# Handschuh.net
KiCad netlist of a schematic drawn in EAGLE
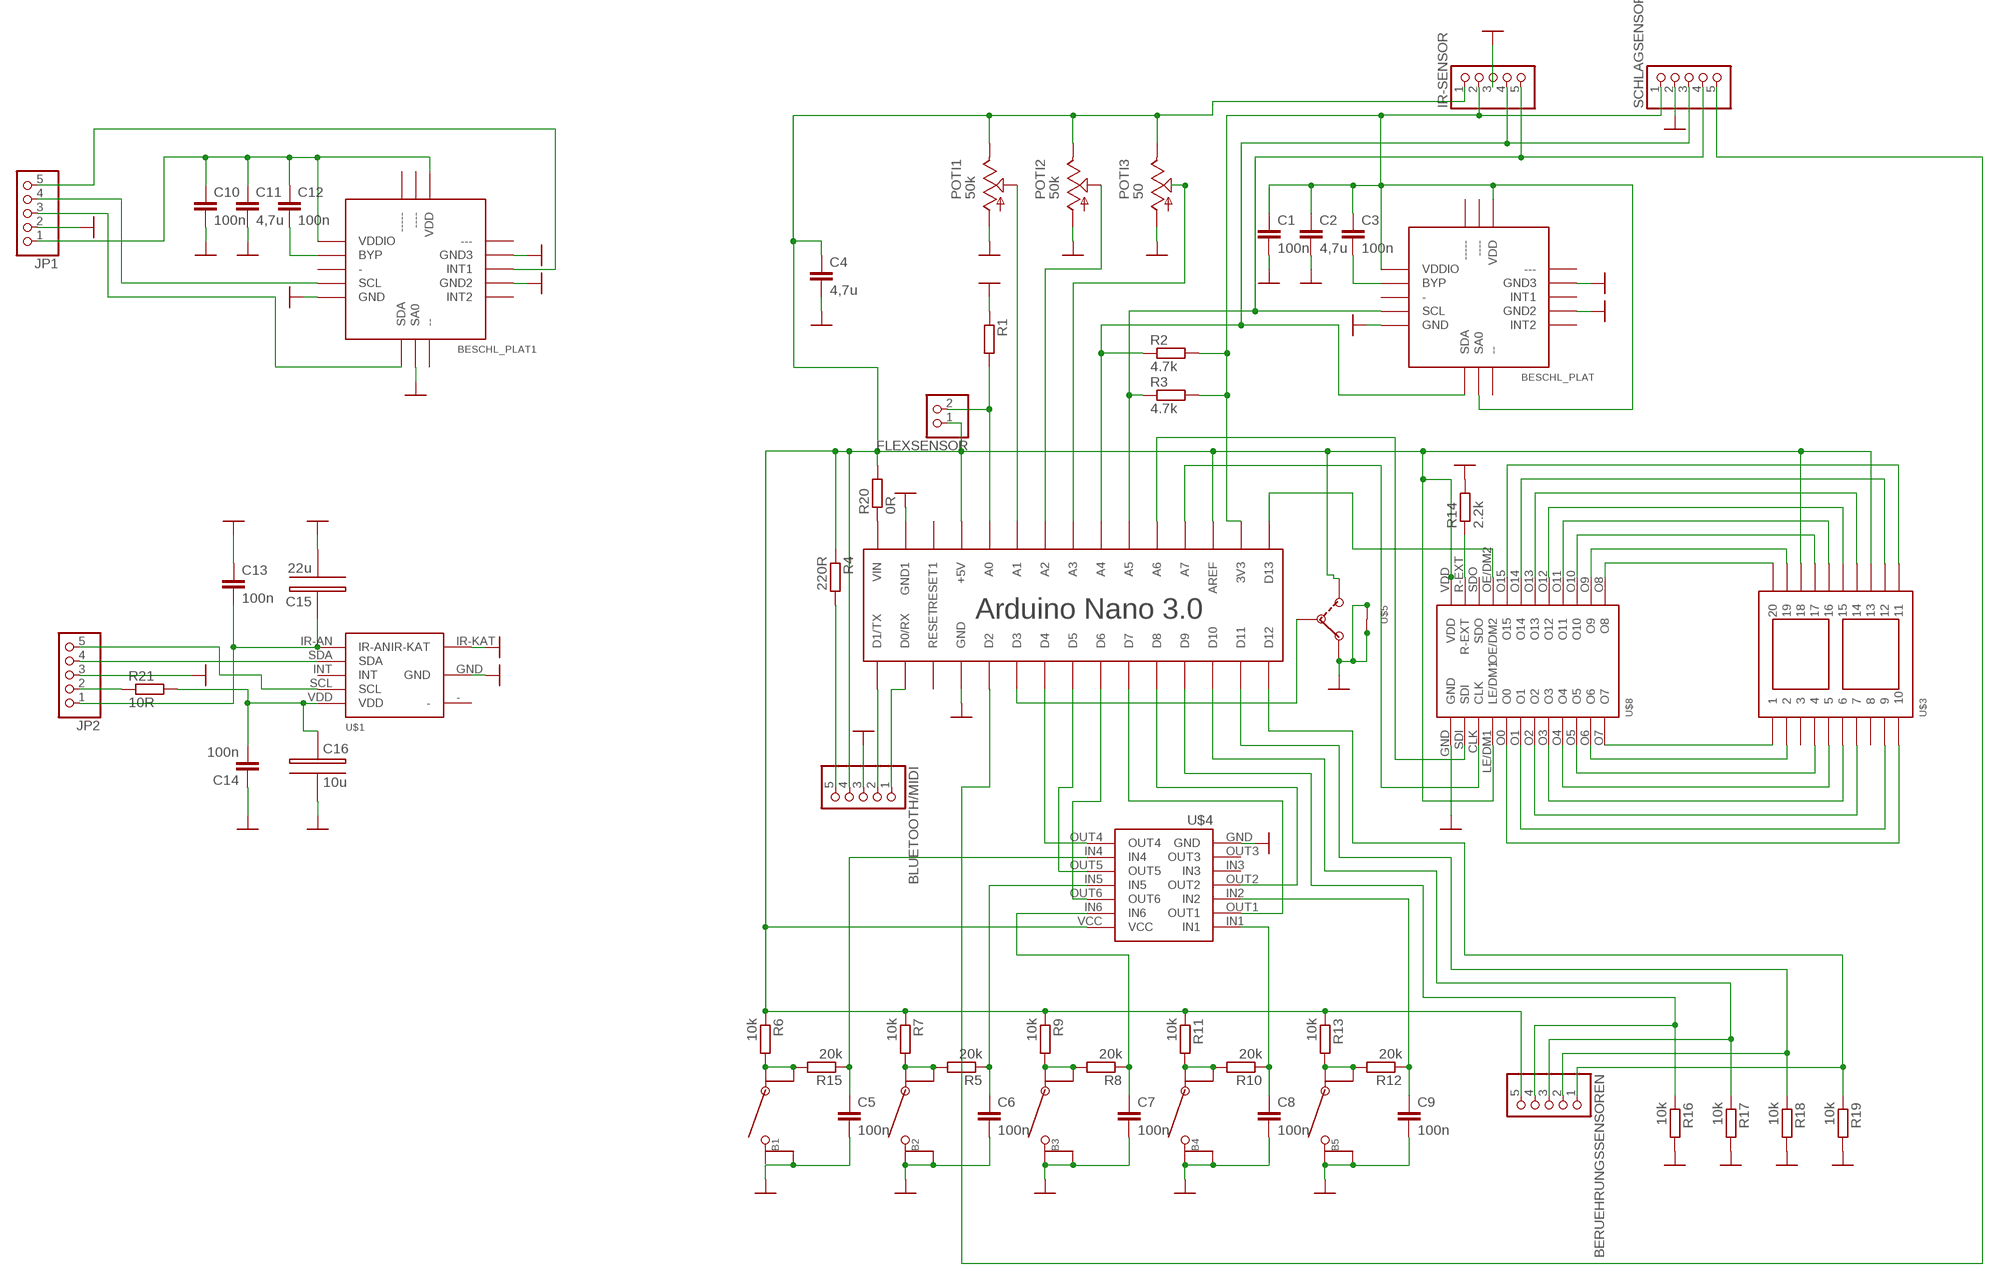
[diagram p0: schematic, sheet 1]

(export (version "E")
  (design (tool "Eeschema 10.0.6"))
  (components
    (comp (ref "B1")
      (value "BUTTON")
      (footprint "eagle-import:BUTTON")
      (libsource (lib "eagle-import") (part "BUTTON"))
    )
    (comp (ref "B2")
      (value "BUTTON")
      (footprint "eagle-import:BUTTON")
      (libsource (lib "eagle-import") (part "BUTTON"))
    )
    (comp (ref "B3")
      (value "BUTTON")
      (footprint "eagle-import:BUTTON")
      (libsource (lib "eagle-import") (part "BUTTON"))
    )
    (comp (ref "B4")
      (value "BUTTON")
      (footprint "eagle-import:BUTTON")
      (libsource (lib "eagle-import") (part "BUTTON"))
    )
    (comp (ref "B5")
      (value "BUTTON")
      (footprint "eagle-import:BUTTON")
      (libsource (lib "eagle-import") (part "BUTTON"))
    )
    (comp (ref "BERUEHRUNGSSENSOREN")
      (value "PINHD-1X5/90")
      (footprint "eagle-import:1X05_90")
      (libsource (lib "eagle-import") (part "PINHD-1X5/90"))
    )
    (comp (ref "BESCHL_PLAT")
      (value "BESCHLEUNIGSUNGSSENSOR")
      (footprint "eagle-import:BESCHLEUNIGUNGSSENSOR")
      (libsource (lib "eagle-import") (part "BESCHLEUNIGSUNGSSENSOR"))
    )
    (comp (ref "BESCHL_PLAT1")
      (value "BESCHLEUNIGSUNGSSENSOR")
      (footprint "eagle-import:BESCHLEUNIGUNGSSENSOR")
      (libsource (lib "eagle-import") (part "BESCHLEUNIGSUNGSSENSOR"))
    )
    (comp (ref "BLUETOOTH/MIDI")
      (value "PINHD-1X5/90")
      (footprint "eagle-import:1X05_90")
      (libsource (lib "eagle-import") (part "PINHD-1X5/90"))
    )
    (comp (ref "C1")
      (value "100n")
      (footprint "eagle-import:C0805")
      (libsource (lib "eagle-import") (part "C-EUC0805"))
    )
    (comp (ref "C2")
      (value "4,7u")
      (footprint "eagle-import:C0805")
      (libsource (lib "eagle-import") (part "C-EUC0805"))
    )
    (comp (ref "C3")
      (value "100n")
      (footprint "eagle-import:C0805")
      (libsource (lib "eagle-import") (part "C-EUC0805"))
    )
    (comp (ref "C4")
      (value "4,7u")
      (footprint "eagle-import:C0805")
      (libsource (lib "eagle-import") (part "C-EUC0805"))
    )
    (comp (ref "C5")
      (value "100n")
      (footprint "eagle-import:C0805")
      (libsource (lib "eagle-import") (part "C-EUC0805"))
    )
    (comp (ref "C6")
      (value "100n")
      (footprint "eagle-import:C0805")
      (libsource (lib "eagle-import") (part "C-EUC0805"))
    )
    (comp (ref "C7")
      (value "100n")
      (footprint "eagle-import:C0805")
      (libsource (lib "eagle-import") (part "C-EUC0805"))
    )
    (comp (ref "C8")
      (value "100n")
      (footprint "eagle-import:C0805")
      (libsource (lib "eagle-import") (part "C-EUC0805"))
    )
    (comp (ref "C9")
      (value "100n")
      (footprint "eagle-import:C0805")
      (libsource (lib "eagle-import") (part "C-EUC0805"))
    )
    (comp (ref "C10")
      (value "100n")
      (footprint "eagle-import:C0805")
      (libsource (lib "eagle-import") (part "C-EUC0805"))
    )
    (comp (ref "C11")
      (value "4,7u")
      (footprint "eagle-import:C0805")
      (libsource (lib "eagle-import") (part "C-EUC0805"))
    )
    (comp (ref "C12")
      (value "100n")
      (footprint "eagle-import:C0805")
      (libsource (lib "eagle-import") (part "C-EUC0805"))
    )
    (comp (ref "C13")
      (value "100n")
      (footprint "eagle-import:C0805")
      (libsource (lib "eagle-import") (part "C-EUC0805"))
    )
    (comp (ref "C14")
      (value "100n")
      (footprint "eagle-import:C0805")
      (libsource (lib "eagle-import") (part "C-EUC0805"))
    )
    (comp (ref "C15")
      (value "22u")
      (footprint "eagle-import:22U-KONDENSATOR")
      (libsource (lib "eagle-import") (part "22U-KONDENSATOR"))
    )
    (comp (ref "C16")
      (value "10u")
      (footprint "eagle-import:22U-KONDENSATOR")
      (libsource (lib "eagle-import") (part "22U-KONDENSATOR"))
    )
    (comp (ref "FLEXSENSOR")
      (value "PINHD-1X2/90")
      (footprint "eagle-import:1X02_90")
      (libsource (lib "eagle-import") (part "PINHD-1X2/90"))
    )
    (comp (ref "IR-SENSOR")
      (value "PINHD-1X5/90")
      (footprint "eagle-import:1X05_90")
      (libsource (lib "eagle-import") (part "PINHD-1X5/90"))
    )
    (comp (ref "JP1")
      (value "PINHD-1X5/90")
      (footprint "eagle-import:1X05_90")
      (libsource (lib "eagle-import") (part "PINHD-1X5/90"))
    )
    (comp (ref "JP2")
      (value "PINHD-1X5/90")
      (footprint "eagle-import:1X05_90")
      (libsource (lib "eagle-import") (part "PINHD-1X5/90"))
    )
    (comp (ref "POTI1")
      (value "50k")
      (footprint "eagle-import:POTI")
      (libsource (lib "eagle-import") (part "POTI"))
    )
    (comp (ref "POTI2")
      (value "50k")
      (footprint "eagle-import:POTI")
      (libsource (lib "eagle-import") (part "POTI"))
    )
    (comp (ref "POTI3")
      (value "50")
      (footprint "eagle-import:POTI")
      (libsource (lib "eagle-import") (part "POTI"))
    )
    (comp (ref "R1")
      (value "R-EU_M0805")
      (footprint "eagle-import:M0805")
      (libsource (lib "eagle-import") (part "R-EU_M0805"))
    )
    (comp (ref "R2")
      (value "4.7k")
      (footprint "eagle-import:M0805")
      (libsource (lib "eagle-import") (part "R-EU_M0805"))
    )
    (comp (ref "R3")
      (value "4.7k")
      (footprint "eagle-import:M0805")
      (libsource (lib "eagle-import") (part "R-EU_M0805"))
    )
    (comp (ref "R4")
      (value "220R")
      (footprint "eagle-import:M0805")
      (libsource (lib "eagle-import") (part "R-EU_M0805"))
    )
    (comp (ref "R5")
      (value "20k")
      (footprint "eagle-import:M0805")
      (libsource (lib "eagle-import") (part "R-EU_M0805"))
    )
    (comp (ref "R6")
      (value "10k")
      (footprint "eagle-import:M0805")
      (libsource (lib "eagle-import") (part "R-EU_M0805"))
    )
    (comp (ref "R7")
      (value "10k")
      (footprint "eagle-import:M0805")
      (libsource (lib "eagle-import") (part "R-EU_M0805"))
    )
    (comp (ref "R8")
      (value "20k")
      (footprint "eagle-import:M0805")
      (libsource (lib "eagle-import") (part "R-EU_M0805"))
    )
    (comp (ref "R9")
      (value "10k")
      (footprint "eagle-import:M0805")
      (libsource (lib "eagle-import") (part "R-EU_M0805"))
    )
    (comp (ref "R10")
      (value "20k")
      (footprint "eagle-import:M0805")
      (libsource (lib "eagle-import") (part "R-EU_M0805"))
    )
    (comp (ref "R11")
      (value "10k")
      (footprint "eagle-import:M0805")
      (libsource (lib "eagle-import") (part "R-EU_M0805"))
    )
    (comp (ref "R12")
      (value "20k")
      (footprint "eagle-import:M0805")
      (libsource (lib "eagle-import") (part "R-EU_M0805"))
    )
    (comp (ref "R13")
      (value "10k")
      (footprint "eagle-import:M0805")
      (libsource (lib "eagle-import") (part "R-EU_M0805"))
    )
    (comp (ref "R14")
      (value "2.2k")
      (footprint "eagle-import:M0805")
      (libsource (lib "eagle-import") (part "R-EU_M0805"))
    )
    (comp (ref "R15")
      (value "20k")
      (footprint "eagle-import:M0805")
      (libsource (lib "eagle-import") (part "R-EU_M0805"))
    )
    (comp (ref "R16")
      (value "10k")
      (footprint "eagle-import:M0805")
      (libsource (lib "eagle-import") (part "R-EU_M0805"))
    )
    (comp (ref "R17")
      (value "10k")
      (footprint "eagle-import:M0805")
      (libsource (lib "eagle-import") (part "R-EU_M0805"))
    )
    (comp (ref "R18")
      (value "10k")
      (footprint "eagle-import:M0805")
      (libsource (lib "eagle-import") (part "R-EU_M0805"))
    )
    (comp (ref "R19")
      (value "10k")
      (footprint "eagle-import:M0805")
      (libsource (lib "eagle-import") (part "R-EU_M0805"))
    )
    (comp (ref "R20")
      (value "0R")
      (footprint "eagle-import:M0805")
      (libsource (lib "eagle-import") (part "R-EU_M0805"))
    )
    (comp (ref "R21")
      (value "10R")
      (footprint "eagle-import:M0805")
      (libsource (lib "eagle-import") (part "R-EU_M0805"))
    )
    (comp (ref "SCHLAGSENSOR")
      (value "PINHD-1X5/90")
      (footprint "eagle-import:1X05_90")
      (libsource (lib "eagle-import") (part "PINHD-1X5/90"))
    )
    (comp (ref "U$1")
      (value "IR-SENSOR")
      (footprint "eagle-import:IR-SENSOR")
      (libsource (lib "eagle-import") (part "IR-SENSOR"))
    )
    (comp (ref "U$2")
      (value "ARDUINONANO")
      (footprint "eagle-import:PDIP-32")
      (libsource (lib "eagle-import") (part "ARDUINONANO"))
    )
    (comp (ref "U$3")
      (value "7-SEGMENT")
      (footprint "eagle-import:7-SEGMENT")
      (libsource (lib "eagle-import") (part "7-SEGMENT"))
    )
    (comp (ref "U$4")
      (value "SCHMITT-TRIGGER")
      (footprint "eagle-import:SCHMITT-TRIGGER")
      (libsource (lib "eagle-import") (part "SCHMITT-TRIGGER"))
    )
    (comp (ref "U$5")
      (value "SCHALTER")
      (footprint "eagle-import:SCHALTER")
      (libsource (lib "eagle-import") (part "SCHALTER"))
    )
    (comp (ref "U$8")
      (value "7-SEGMENT-TREIBER")
      (footprint "eagle-import:7-SEGMENT-TREIBER")
      (libsource (lib "eagle-import") (part "7-SEGMENT-TREIBER"))
    )
  )
  (nets
    (net (code "1") (name "Net-(B1-Pad3)") (class "Default")
      (node (ref "B1") (pin "3") (pinfunction "3_3") (pintype "bidirectional"))
      (node (ref "B1") (pin "4") (pinfunction "4_4") (pintype "bidirectional"))
      (node (ref "R15") (pin "2") (pinfunction "2_2") (pintype "passive"))
      (node (ref "R6") (pin "2") (pinfunction "2_2") (pintype "passive"))
    )
    (net (code "2") (name "Net-(B2-Pad3)") (class "Default")
      (node (ref "B2") (pin "3") (pinfunction "3_3") (pintype "bidirectional"))
      (node (ref "B2") (pin "4") (pinfunction "4_4") (pintype "bidirectional"))
      (node (ref "R5") (pin "2") (pinfunction "2_2") (pintype "passive"))
      (node (ref "R7") (pin "2") (pinfunction "2_2") (pintype "passive"))
    )
    (net (code "3") (name "Net-(B3-Pad3)") (class "Default")
      (node (ref "B3") (pin "3") (pinfunction "3_3") (pintype "bidirectional"))
      (node (ref "B3") (pin "4") (pinfunction "4_4") (pintype "bidirectional"))
      (node (ref "R8") (pin "2") (pinfunction "2_2") (pintype "passive"))
      (node (ref "R9") (pin "2") (pinfunction "2_2") (pintype "passive"))
    )
    (net (code "4") (name "Net-(B4-Pad3)") (class "Default")
      (node (ref "B4") (pin "3") (pinfunction "3_3") (pintype "bidirectional"))
      (node (ref "B4") (pin "4") (pinfunction "4_4") (pintype "bidirectional"))
      (node (ref "R10") (pin "2") (pinfunction "2_2") (pintype "passive"))
      (node (ref "R11") (pin "2") (pinfunction "2_2") (pintype "passive"))
    )
    (net (code "5") (name "Net-(B5-Pad3)") (class "Default")
      (node (ref "B5") (pin "3") (pinfunction "3_3") (pintype "bidirectional"))
      (node (ref "B5") (pin "4") (pinfunction "4_4") (pintype "bidirectional"))
      (node (ref "R12") (pin "2") (pinfunction "2_2") (pintype "passive"))
      (node (ref "R13") (pin "2") (pinfunction "2_2") (pintype "passive"))
    )
    (net (code "6") (name "Net-(BERUEHRUNGSSENSOREN-Pad1)") (class "Default")
      (node (ref "BERUEHRUNGSSENSOREN") (pin "1") (pinfunction "1_1") (pintype "passive"))
      (node (ref "R19") (pin "1") (pinfunction "1_1") (pintype "passive"))
      (node (ref "U$2") (pin "D12") (pinfunction "D12_D12") (pintype "bidirectional"))
    )
    (net (code "7") (name "Net-(BERUEHRUNGSSENSOREN-Pad2)") (class "Default")
      (node (ref "BERUEHRUNGSSENSOREN") (pin "2") (pinfunction "2_2") (pintype "passive"))
      (node (ref "R18") (pin "1") (pinfunction "1_1") (pintype "passive"))
      (node (ref "U$2") (pin "D11") (pinfunction "D11_D11") (pintype "bidirectional"))
    )
    (net (code "8") (name "Net-(BERUEHRUNGSSENSOREN-Pad3)") (class "Default")
      (node (ref "BERUEHRUNGSSENSOREN") (pin "3") (pinfunction "3_3") (pintype "passive"))
      (node (ref "R17") (pin "1") (pinfunction "1_1") (pintype "passive"))
      (node (ref "U$2") (pin "D10") (pinfunction "D10_D10") (pintype "bidirectional"))
    )
    (net (code "9") (name "Net-(BERUEHRUNGSSENSOREN-Pad4)") (class "Default")
      (node (ref "BERUEHRUNGSSENSOREN") (pin "4") (pinfunction "4_4") (pintype "passive"))
      (node (ref "R16") (pin "1") (pinfunction "1_1") (pintype "passive"))
      (node (ref "U$2") (pin "D9") (pinfunction "D9_D9") (pintype "bidirectional"))
    )
    (net (code "10") (name "Net-(BERUEHRUNGSSENSOREN-Pad5)") (class "Default")
      (node (ref "BERUEHRUNGSSENSOREN") (pin "5") (pinfunction "5_5") (pintype "passive"))
      (node (ref "BLUETOOTH/MIDI") (pin "4") (pinfunction "4_4") (pintype "passive"))
      (node (ref "C4") (pin "1") (pinfunction "1_1") (pintype "passive"))
      (node (ref "FLEXSENSOR") (pin "1") (pinfunction "1_1") (pintype "passive"))
      (node (ref "IR-SENSOR") (pin "1") (pinfunction "1_1") (pintype "passive"))
      (node (ref "POTI1") (pin "VCC") (pinfunction "VCC_VCC") (pintype "passive"))
      (node (ref "POTI2") (pin "VCC") (pinfunction "VCC_VCC") (pintype "passive"))
      (node (ref "POTI3") (pin "VCC") (pinfunction "VCC_VCC") (pintype "passive"))
      (node (ref "R11") (pin "1") (pinfunction "1_1") (pintype "passive"))
      (node (ref "R13") (pin "1") (pinfunction "1_1") (pintype "passive"))
      (node (ref "R20") (pin "2") (pinfunction "2_2") (pintype "passive"))
      (node (ref "R4") (pin "1") (pinfunction "1_1") (pintype "passive"))
      (node (ref "R6") (pin "1") (pinfunction "1_1") (pintype "passive"))
      (node (ref "R7") (pin "1") (pinfunction "1_1") (pintype "passive"))
      (node (ref "R9") (pin "1") (pinfunction "1_1") (pintype "passive"))
      (node (ref "U$2") (pin "+5V") (pinfunction "+5V_+5V") (pintype "bidirectional"))
      (node (ref "U$2") (pin "AREF") (pinfunction "AREF_AREF") (pintype "bidirectional"))
      (node (ref "U$3") (pin "13") (pinfunction "13_13") (pintype "bidirectional"))
      (node (ref "U$3") (pin "18") (pinfunction "18_18") (pintype "bidirectional"))
      (node (ref "U$4") (pin "VCC") (pinfunction "VCC_VCC") (pintype "bidirectional"))
      (node (ref "U$5") (pin "3") (pinfunction "3_3") (pintype "bidirectional"))
      (node (ref "U$8") (pin "LE/DM1") (pinfunction "LE/DM1_LE/DM1") (pintype "bidirectional"))
      (node (ref "U$8") (pin "VDD") (pinfunction "VDD_VDD") (pintype "bidirectional"))
    )
    (net (code "11") (name "Net-(BESCHL_PLAT-PadBYP)") (class "Default")
      (node (ref "BESCHL_PLAT") (pin "BYP") (pinfunction "BYP_BYP") (pintype "bidirectional"))
      (node (ref "C3") (pin "2") (pinfunction "2_2") (pintype "passive"))
    )
    (net (code "12") (name "Net-(BESCHL_PLAT-PadSA0)") (class "Default")
      (node (ref "BESCHL_PLAT") (pin "SA0") (pinfunction "SA0_SA0") (pintype "bidirectional"))
      (node (ref "BESCHL_PLAT") (pin "VDD") (pinfunction "VDD_VDD") (pintype "bidirectional"))
      (node (ref "BESCHL_PLAT") (pin "VDDIO") (pinfunction "VDDIO_VDDIO") (pintype "bidirectional"))
      (node (ref "C1") (pin "1") (pinfunction "1_1") (pintype "passive"))
      (node (ref "C2") (pin "1") (pinfunction "1_1") (pintype "passive"))
      (node (ref "C3") (pin "1") (pinfunction "1_1") (pintype "passive"))
      (node (ref "IR-SENSOR") (pin "2") (pinfunction "2_2") (pintype "passive"))
      (node (ref "R2") (pin "2") (pinfunction "2_2") (pintype "passive"))
      (node (ref "R3") (pin "2") (pinfunction "2_2") (pintype "passive"))
      (node (ref "SCHLAGSENSOR") (pin "1") (pinfunction "1_1") (pintype "passive"))
      (node (ref "U$2") (pin "3V3") (pinfunction "3V3_3V3") (pintype "bidirectional"))
    )
    (net (code "13") (name "Net-(BESCHL_PLAT-PadSCL)") (class "Default")
      (node (ref "BESCHL_PLAT") (pin "SCL") (pinfunction "SCL_SCL") (pintype "bidirectional"))
      (node (ref "IR-SENSOR") (pin "5") (pinfunction "5_5") (pintype "passive"))
      (node (ref "R3") (pin "1") (pinfunction "1_1") (pintype "passive"))
      (node (ref "SCHLAGSENSOR") (pin "4") (pinfunction "4_4") (pintype "passive"))
      (node (ref "U$2") (pin "A5") (pinfunction "A5_A5") (pintype "bidirectional"))
    )
    (net (code "14") (name "Net-(BESCHL_PLAT-PadSDA)") (class "Default")
      (node (ref "BESCHL_PLAT") (pin "SDA") (pinfunction "SDA_SDA") (pintype "bidirectional"))
      (node (ref "IR-SENSOR") (pin "4") (pinfunction "4_4") (pintype "passive"))
      (node (ref "R2") (pin "1") (pinfunction "1_1") (pintype "passive"))
      (node (ref "SCHLAGSENSOR") (pin "3") (pinfunction "3_3") (pintype "passive"))
      (node (ref "U$2") (pin "A4") (pinfunction "A4_A4") (pintype "bidirectional"))
    )
    (net (code "15") (name "Net-(BESCHL_PLAT1-PadBYP)") (class "Default")
      (node (ref "BESCHL_PLAT1") (pin "BYP") (pinfunction "BYP_BYP") (pintype "bidirectional"))
      (node (ref "C12") (pin "2") (pinfunction "2_2") (pintype "passive"))
    )
    (net (code "16") (name "Net-(BESCHL_PLAT1-PadINT1)") (class "Default")
      (node (ref "BESCHL_PLAT1") (pin "INT1") (pinfunction "INT1_INT1") (pintype "bidirectional"))
      (node (ref "JP1") (pin "5") (pinfunction "5_5") (pintype "passive"))
    )
    (net (code "17") (name "Net-(BESCHL_PLAT1-PadSCL)") (class "Default")
      (node (ref "BESCHL_PLAT1") (pin "SCL") (pinfunction "SCL_SCL") (pintype "bidirectional"))
      (node (ref "JP1") (pin "4") (pinfunction "4_4") (pintype "passive"))
    )
    (net (code "18") (name "Net-(BESCHL_PLAT1-PadSDA)") (class "Default")
      (node (ref "BESCHL_PLAT1") (pin "SDA") (pinfunction "SDA_SDA") (pintype "bidirectional"))
      (node (ref "JP1") (pin "3") (pinfunction "3_3") (pintype "passive"))
    )
    (net (code "19") (name "Net-(BESCHL_PLAT1-PadVDD)") (class "Default")
      (node (ref "BESCHL_PLAT1") (pin "VDD") (pinfunction "VDD_VDD") (pintype "bidirectional"))
      (node (ref "BESCHL_PLAT1") (pin "VDDIO") (pinfunction "VDDIO_VDDIO") (pintype "bidirectional"))
      (node (ref "C10") (pin "1") (pinfunction "1_1") (pintype "passive"))
      (node (ref "C11") (pin "1") (pinfunction "1_1") (pintype "passive"))
      (node (ref "C12") (pin "1") (pinfunction "1_1") (pintype "passive"))
      (node (ref "JP1") (pin "1") (pinfunction "1_1") (pintype "passive"))
    )
    (net (code "20") (name "Net-(BLUETOOTH/MIDI-Pad1)") (class "Default")
      (node (ref "BLUETOOTH/MIDI") (pin "1") (pinfunction "1_1") (pintype "passive"))
      (node (ref "U$2") (pin "D0/RX") (pinfunction "D0/RX_D0/RX") (pintype "bidirectional"))
    )
    (net (code "21") (name "Net-(BLUETOOTH/MIDI-Pad2)") (class "Default")
      (node (ref "BLUETOOTH/MIDI") (pin "2") (pinfunction "2_2") (pintype "passive"))
      (node (ref "U$2") (pin "D1/TX") (pinfunction "D1/TX_D1/TX") (pintype "bidirectional"))
    )
    (net (code "22") (name "Net-(BLUETOOTH/MIDI-Pad5)") (class "Default")
      (node (ref "BLUETOOTH/MIDI") (pin "5") (pinfunction "5_5") (pintype "passive"))
      (node (ref "R4") (pin "2") (pinfunction "2_2") (pintype "passive"))
    )
    (net (code "23") (name "Net-(C5-Pad1)") (class "Default")
      (node (ref "C5") (pin "1") (pinfunction "1_1") (pintype "passive"))
      (node (ref "R15") (pin "1") (pinfunction "1_1") (pintype "passive"))
      (node (ref "U$4") (pin "IN4") (pinfunction "IN4_IN4") (pintype "bidirectional"))
    )
    (net (code "24") (name "Net-(C6-Pad1)") (class "Default")
      (node (ref "C6") (pin "1") (pinfunction "1_1") (pintype "passive"))
      (node (ref "R5") (pin "1") (pinfunction "1_1") (pintype "passive"))
      (node (ref "U$4") (pin "IN5") (pinfunction "IN5_IN5") (pintype "bidirectional"))
    )
    (net (code "25") (name "Net-(C7-Pad1)") (class "Default")
      (node (ref "C7") (pin "1") (pinfunction "1_1") (pintype "passive"))
      (node (ref "R8") (pin "1") (pinfunction "1_1") (pintype "passive"))
      (node (ref "U$4") (pin "IN6") (pinfunction "IN6_IN6") (pintype "bidirectional"))
    )
    (net (code "26") (name "Net-(C8-Pad1)") (class "Default")
      (node (ref "C8") (pin "1") (pinfunction "1_1") (pintype "passive"))
      (node (ref "R10") (pin "1") (pinfunction "1_1") (pintype "passive"))
      (node (ref "U$4") (pin "IN1") (pinfunction "IN1_IN1") (pintype "bidirectional"))
    )
    (net (code "27") (name "Net-(C9-Pad1)") (class "Default")
      (node (ref "C9") (pin "1") (pinfunction "1_1") (pintype "passive"))
      (node (ref "R12") (pin "1") (pinfunction "1_1") (pintype "passive"))
      (node (ref "U$4") (pin "IN2") (pinfunction "IN2_IN2") (pintype "bidirectional"))
    )
    (net (code "28") (name "Net-(C13-Pad2)") (class "Default")
      (node (ref "C13") (pin "2") (pinfunction "2_2") (pintype "passive"))
      (node (ref "C15") (pin "+") (pinfunction "+_+") (pintype "bidirectional"))
      (node (ref "JP2") (pin "1") (pinfunction "1_1") (pintype "passive"))
      (node (ref "U$1") (pin "IR-AN") (pinfunction "IR-AN_IR-AN") (pintype "bidirectional"))
    )
    (net (code "29") (name "Net-(C14-Pad2)") (class "Default")
      (node (ref "C14") (pin "2") (pinfunction "2_2") (pintype "passive"))
      (node (ref "C16") (pin "+") (pinfunction "+_+") (pintype "bidirectional"))
      (node (ref "R21") (pin "2") (pinfunction "2_2") (pintype "passive"))
      (node (ref "U$1") (pin "VDD") (pinfunction "VDD_VDD") (pintype "bidirectional"))
    )
    (net (code "30") (name "Net-(FLEXSENSOR-Pad2)") (class "Default")
      (node (ref "FLEXSENSOR") (pin "2") (pinfunction "2_2") (pintype "passive"))
      (node (ref "R1") (pin "2") (pinfunction "2_2") (pintype "passive"))
      (node (ref "U$2") (pin "A0") (pinfunction "A0_A0") (pintype "bidirectional"))
    )
    (net (code "31") (name "Net-(JP2-Pad2)") (class "Default")
      (node (ref "JP2") (pin "2") (pinfunction "2_2") (pintype "passive"))
      (node (ref "R21") (pin "1") (pinfunction "1_1") (pintype "passive"))
    )
    (net (code "32") (name "Net-(JP2-Pad4)") (class "Default")
      (node (ref "JP2") (pin "4") (pinfunction "4_4") (pintype "passive"))
      (node (ref "U$1") (pin "SDA") (pinfunction "SDA_SDA") (pintype "bidirectional"))
    )
    (net (code "33") (name "Net-(JP2-Pad5)") (class "Default")
      (node (ref "JP2") (pin "5") (pinfunction "5_5") (pintype "passive"))
      (node (ref "U$1") (pin "SCL") (pinfunction "SCL_SCL") (pintype "bidirectional"))
    )
    (net (code "34") (name "Net-(POTI1-PadVALUE)") (class "Default")
      (node (ref "POTI1") (pin "VALUE") (pinfunction "VALUE_VALUE") (pintype "passive"))
      (node (ref "U$2") (pin "A1") (pinfunction "A1_A1") (pintype "bidirectional"))
    )
    (net (code "35") (name "Net-(POTI2-PadVALUE)") (class "Default")
      (node (ref "POTI2") (pin "VALUE") (pinfunction "VALUE_VALUE") (pintype "passive"))
      (node (ref "U$2") (pin "A2") (pinfunction "A2_A2") (pintype "bidirectional"))
    )
    (net (code "36") (name "Net-(POTI3-PadVALUE)") (class "Default")
      (node (ref "POTI3") (pin "VALUE") (pinfunction "VALUE_VALUE") (pintype "passive"))
      (node (ref "U$2") (pin "A3") (pinfunction "A3_A3") (pintype "bidirectional"))
    )
    (net (code "37") (name "Net-(R14-Pad1)") (class "Default")
      (node (ref "R14") (pin "1") (pinfunction "1_1") (pintype "passive"))
      (node (ref "U$8") (pin "R-EXT") (pinfunction "R-EXT_R-EXT") (pintype "bidirectional"))
    )
    (net (code "38") (name "Net-(R20-Pad1)") (class "Default")
      (node (ref "R20") (pin "1") (pinfunction "1_1") (pintype "passive"))
      (node (ref "U$2") (pin "VIN") (pinfunction "VIN_VIN") (pintype "bidirectional"))
    )
    (net (code "39") (name "Net-(SCHLAGSENSOR-Pad5)") (class "Default")
      (node (ref "SCHLAGSENSOR") (pin "5") (pinfunction "5_5") (pintype "passive"))
      (node (ref "U$2") (pin "D2") (pinfunction "D2_D2") (pintype "bidirectional"))
    )
    (net (code "40") (name "Net-(U$2-PadA6)") (class "Default")
      (node (ref "U$2") (pin "A6") (pinfunction "A6_A6") (pintype "bidirectional"))
      (node (ref "U$8") (pin "SDI") (pinfunction "SDI_SDI") (pintype "bidirectional"))
    )
    (net (code "41") (name "Net-(U$2-PadA7)") (class "Default")
      (node (ref "U$2") (pin "A7") (pinfunction "A7_A7") (pintype "bidirectional"))
      (node (ref "U$8") (pin "CLK") (pinfunction "CLK_CLK") (pintype "bidirectional"))
    )
    (net (code "42") (name "Net-(U$2-PadD3)") (class "Default")
      (node (ref "U$2") (pin "D3") (pinfunction "D3_D3") (pintype "bidirectional"))
      (node (ref "U$5") (pin "2") (pinfunction "2_2") (pintype "bidirectional"))
    )
    (net (code "43") (name "Net-(U$2-PadD4)") (class "Default")
      (node (ref "U$2") (pin "D4") (pinfunction "D4_D4") (pintype "bidirectional"))
      (node (ref "U$4") (pin "OUT4") (pinfunction "OUT4_OUT4") (pintype "bidirectional"))
    )
    (net (code "44") (name "Net-(U$2-PadD5)") (class "Default")
      (node (ref "U$2") (pin "D5") (pinfunction "D5_D5") (pintype "bidirectional"))
      (node (ref "U$4") (pin "OUT5") (pinfunction "OUT5_OUT5") (pintype "bidirectional"))
    )
    (net (code "45") (name "Net-(U$2-PadD6)") (class "Default")
      (node (ref "U$2") (pin "D6") (pinfunction "D6_D6") (pintype "bidirectional"))
      (node (ref "U$4") (pin "OUT6") (pinfunction "OUT6_OUT6") (pintype "bidirectional"))
    )
    (net (code "46") (name "Net-(U$2-PadD7)") (class "Default")
      (node (ref "U$2") (pin "D7") (pinfunction "D7_D7") (pintype "bidirectional"))
      (node (ref "U$4") (pin "OUT1") (pinfunction "OUT1_OUT1") (pintype "bidirectional"))
    )
    (net (code "47") (name "Net-(U$2-PadD8)") (class "Default")
      (node (ref "U$2") (pin "D8") (pinfunction "D8_D8") (pintype "bidirectional"))
      (node (ref "U$4") (pin "OUT2") (pinfunction "OUT2_OUT2") (pintype "bidirectional"))
    )
    (net (code "48") (name "Net-(U$2-PadD13)") (class "Default")
      (node (ref "U$2") (pin "D13") (pinfunction "D13_D13") (pintype "bidirectional"))
      (node (ref "U$8") (pin "OE/DM2") (pinfunction "OE/DM2_OE/DM2") (pintype "bidirectional"))
    )
    (net (code "49") (name "Net-(U$3-Pad1)") (class "Default")
      (node (ref "U$3") (pin "1") (pinfunction "1_1") (pintype "bidirectional"))
      (node (ref "U$8") (pin "O7") (pinfunction "O7_O7") (pintype "bidirectional"))
    )
    (net (code "50") (name "Net-(U$3-Pad2)") (class "Default")
      (node (ref "U$3") (pin "2") (pinfunction "2_2") (pintype "bidirectional"))
      (node (ref "U$8") (pin "O6") (pinfunction "O6_O6") (pintype "bidirectional"))
    )
    (net (code "51") (name "Net-(U$3-Pad4)") (class "Default")
      (node (ref "U$3") (pin "4") (pinfunction "4_4") (pintype "bidirectional"))
      (node (ref "U$8") (pin "O5") (pinfunction "O5_O5") (pintype "bidirectional"))
    )
    (net (code "52") (name "Net-(U$3-Pad5)") (class "Default")
      (node (ref "U$3") (pin "5") (pinfunction "5_5") (pintype "bidirectional"))
      (node (ref "U$8") (pin "O4") (pinfunction "O4_O4") (pintype "bidirectional"))
    )
    (net (code "53") (name "Net-(U$3-Pad6)") (class "Default")
      (node (ref "U$3") (pin "6") (pinfunction "6_6") (pintype "bidirectional"))
      (node (ref "U$8") (pin "O3") (pinfunction "O3_O3") (pintype "bidirectional"))
    )
    (net (code "54") (name "Net-(U$3-Pad7)") (class "Default")
      (node (ref "U$3") (pin "7") (pinfunction "7_7") (pintype "bidirectional"))
      (node (ref "U$8") (pin "O2") (pinfunction "O2_O2") (pintype "bidirectional"))
    )
    (net (code "55") (name "Net-(U$3-Pad9)") (class "Default")
      (node (ref "U$3") (pin "9") (pinfunction "9_9") (pintype "bidirectional"))
      (node (ref "U$8") (pin "O1") (pinfunction "O1_O1") (pintype "bidirectional"))
    )
    (net (code "56") (name "Net-(U$3-Pad10)") (class "Default")
      (node (ref "U$3") (pin "10") (pinfunction "10_10") (pintype "bidirectional"))
      (node (ref "U$8") (pin "O0") (pinfunction "O0_O0") (pintype "bidirectional"))
    )
    (net (code "57") (name "Net-(U$3-Pad11)") (class "Default")
      (node (ref "U$3") (pin "11") (pinfunction "11_11") (pintype "bidirectional"))
      (node (ref "U$8") (pin "O15") (pinfunction "O15_O15") (pintype "bidirectional"))
    )
    (net (code "58") (name "Net-(U$3-Pad12)") (class "Default")
      (node (ref "U$3") (pin "12") (pinfunction "12_12") (pintype "bidirectional"))
      (node (ref "U$8") (pin "O14") (pinfunction "O14_O14") (pintype "bidirectional"))
    )
    (net (code "59") (name "Net-(U$3-Pad14)") (class "Default")
      (node (ref "U$3") (pin "14") (pinfunction "14_14") (pintype "bidirectional"))
      (node (ref "U$8") (pin "O13") (pinfunction "O13_O13") (pintype "bidirectional"))
    )
    (net (code "60") (name "Net-(U$3-Pad15)") (class "Default")
      (node (ref "U$3") (pin "15") (pinfunction "15_15") (pintype "bidirectional"))
      (node (ref "U$8") (pin "O12") (pinfunction "O12_O12") (pintype "bidirectional"))
    )
    (net (code "61") (name "Net-(U$3-Pad16)") (class "Default")
      (node (ref "U$3") (pin "16") (pinfunction "16_16") (pintype "bidirectional"))
      (node (ref "U$8") (pin "O11") (pinfunction "O11_O11") (pintype "bidirectional"))
    )
    (net (code "62") (name "Net-(U$3-Pad17)") (class "Default")
      (node (ref "U$3") (pin "17") (pinfunction "17_17") (pintype "bidirectional"))
      (node (ref "U$8") (pin "O10") (pinfunction "O10_O10") (pintype "bidirectional"))
    )
    (net (code "63") (name "Net-(U$3-Pad19)") (class "Default")
      (node (ref "U$3") (pin "19") (pinfunction "19_19") (pintype "bidirectional"))
      (node (ref "U$8") (pin "O9") (pinfunction "O9_O9") (pintype "bidirectional"))
    )
    (net (code "64") (name "Net-(U$3-Pad20)") (class "Default")
      (node (ref "U$3") (pin "20") (pinfunction "20_20") (pintype "bidirectional"))
      (node (ref "U$8") (pin "O8") (pinfunction "O8_O8") (pintype "bidirectional"))
    )
    (net (code "65") (name "POWER_SUPPLY1_GND") (class "Default")
      (node (ref "B1") (pin "2") (pinfunction "2_2") (pintype "bidirectional"))
      (node (ref "B2") (pin "2") (pinfunction "2_2") (pintype "bidirectional"))
      (node (ref "B3") (pin "2") (pinfunction "2_2") (pintype "bidirectional"))
      (node (ref "B4") (pin "2") (pinfunction "2_2") (pintype "bidirectional"))
      (node (ref "B5") (pin "2") (pinfunction "2_2") (pintype "bidirectional"))
      (node (ref "BESCHL_PLAT") (pin "GND") (pinfunction "GND_GND") (pintype "bidirectional"))
      (node (ref "BESCHL_PLAT") (pin "GND2") (pinfunction "GND2_GND2") (pintype "bidirectional"))
      (node (ref "BESCHL_PLAT") (pin "GND3") (pinfunction "GND3_GND3") (pintype "bidirectional"))
      (node (ref "BESCHL_PLAT1") (pin "GND") (pinfunction "GND_GND") (pintype "bidirectional"))
      (node (ref "BESCHL_PLAT1") (pin "GND2") (pinfunction "GND2_GND2") (pintype "bidirectional"))
      (node (ref "BESCHL_PLAT1") (pin "GND3") (pinfunction "GND3_GND3") (pintype "bidirectional"))
      (node (ref "BESCHL_PLAT1") (pin "SA0") (pinfunction "SA0_SA0") (pintype "bidirectional"))
      (node (ref "BLUETOOTH/MIDI") (pin "3") (pinfunction "3_3") (pintype "passive"))
      (node (ref "C1") (pin "2") (pinfunction "2_2") (pintype "passive"))
      (node (ref "C10") (pin "2") (pinfunction "2_2") (pintype "passive"))
      (node (ref "C11") (pin "2") (pinfunction "2_2") (pintype "passive"))
      (node (ref "C13") (pin "1") (pinfunction "1_1") (pintype "passive"))
      (node (ref "C14") (pin "1") (pinfunction "1_1") (pintype "passive"))
      (node (ref "C15") (pin "-") (pinfunction "-_-") (pintype "bidirectional"))
      (node (ref "C16") (pin "-") (pinfunction "-_-") (pintype "bidirectional"))
      (node (ref "C2") (pin "2") (pinfunction "2_2") (pintype "passive"))
      (node (ref "C4") (pin "2") (pinfunction "2_2") (pintype "passive"))
      (node (ref "C5") (pin "2") (pinfunction "2_2") (pintype "passive"))
      (node (ref "C6") (pin "2") (pinfunction "2_2") (pintype "passive"))
      (node (ref "C7") (pin "2") (pinfunction "2_2") (pintype "passive"))
      (node (ref "C8") (pin "2") (pinfunction "2_2") (pintype "passive"))
      (node (ref "C9") (pin "2") (pinfunction "2_2") (pintype "passive"))
      (node (ref "IR-SENSOR") (pin "3") (pinfunction "3_3") (pintype "passive"))
      (node (ref "JP1") (pin "2") (pinfunction "2_2") (pintype "passive"))
      (node (ref "JP2") (pin "3") (pinfunction "3_3") (pintype "passive"))
      (node (ref "POTI1") (pin "GND") (pinfunction "GND_GND") (pintype "passive"))
      (node (ref "POTI2") (pin "GND") (pinfunction "GND_GND") (pintype "passive"))
      (node (ref "POTI3") (pin "GND") (pinfunction "GND_GND") (pintype "passive"))
      (node (ref "R1") (pin "1") (pinfunction "1_1") (pintype "passive"))
      (node (ref "R14") (pin "2") (pinfunction "2_2") (pintype "passive"))
      (node (ref "R16") (pin "2") (pinfunction "2_2") (pintype "passive"))
      (node (ref "R17") (pin "2") (pinfunction "2_2") (pintype "passive"))
      (node (ref "R18") (pin "2") (pinfunction "2_2") (pintype "passive"))
      (node (ref "R19") (pin "2") (pinfunction "2_2") (pintype "passive"))
      (node (ref "SCHLAGSENSOR") (pin "2") (pinfunction "2_2") (pintype "passive"))
      (node (ref "U$1") (pin "GND") (pinfunction "GND_GND") (pintype "bidirectional"))
      (node (ref "U$1") (pin "IR-KAT") (pinfunction "IR-KAT_IR-KAT") (pintype "bidirectional"))
      (node (ref "U$2") (pin "GND") (pinfunction "GND_GND") (pintype "bidirectional"))
      (node (ref "U$2") (pin "GND1") (pinfunction "GND1_GND1") (pintype "bidirectional"))
      (node (ref "U$4") (pin "GND") (pinfunction "GND_GND") (pintype "bidirectional"))
      (node (ref "U$5") (pin "1") (pinfunction "1_1") (pintype "bidirectional"))
      (node (ref "U$5") (pin "4") (pinfunction "4_4") (pintype "bidirectional"))
      (node (ref "U$5") (pin "5") (pinfunction "5_5") (pintype "bidirectional"))
      (node (ref "U$8") (pin "GND") (pinfunction "GND_GND") (pintype "bidirectional"))
    )
    (net (code "66") (name "unconnected-(B1-Pad1)") (class "Default")
      (node (ref "B1") (pin "1") (pinfunction "1_1") (pintype "bidirectional"))
    )
    (net (code "67") (name "unconnected-(B2-Pad1)") (class "Default")
      (node (ref "B2") (pin "1") (pinfunction "1_1") (pintype "bidirectional"))
    )
    (net (code "68") (name "unconnected-(B3-Pad1)") (class "Default")
      (node (ref "B3") (pin "1") (pinfunction "1_1") (pintype "bidirectional"))
    )
    (net (code "69") (name "unconnected-(B4-Pad1)") (class "Default")
      (node (ref "B4") (pin "1") (pinfunction "1_1") (pintype "bidirectional"))
    )
    (net (code "70") (name "unconnected-(B5-Pad1)") (class "Default")
      (node (ref "B5") (pin "1") (pinfunction "1_1") (pintype "bidirectional"))
    )
    (net (code "71") (name "unconnected-(BESCHL_PLAT-Pad-)") (class "Default")
      (node (ref "BESCHL_PLAT") (pin "-") (pinfunction "-_-") (pintype "bidirectional"))
    )
    (net (code "72") (name "unconnected-(BESCHL_PLAT-Pad--)") (class "Default")
      (node (ref "BESCHL_PLAT") (pin "--") (pinfunction "--_--") (pintype "bidirectional"))
    )
    (net (code "73") (name "unconnected-(BESCHL_PLAT-Pad---)") (class "Default")
      (node (ref "BESCHL_PLAT") (pin "---") (pinfunction "---_---") (pintype "bidirectional"))
    )
    (net (code "74") (name "unconnected-(BESCHL_PLAT-Pad----)") (class "Default")
      (node (ref "BESCHL_PLAT") (pin "----") (pinfunction "----_----") (pintype "bidirectional"))
    )
    (net (code "75") (name "unconnected-(BESCHL_PLAT-Pad-----)") (class "Default")
      (node (ref "BESCHL_PLAT") (pin "-----") (pinfunction "-----_-----") (pintype "bidirectional"))
    )
    (net (code "76") (name "unconnected-(BESCHL_PLAT-PadINT1)") (class "Default")
      (node (ref "BESCHL_PLAT") (pin "INT1") (pinfunction "INT1_INT1") (pintype "bidirectional"))
    )
    (net (code "77") (name "unconnected-(BESCHL_PLAT-PadINT2)") (class "Default")
      (node (ref "BESCHL_PLAT") (pin "INT2") (pinfunction "INT2_INT2") (pintype "bidirectional"))
    )
    (net (code "78") (name "unconnected-(BESCHL_PLAT1-Pad-)") (class "Default")
      (node (ref "BESCHL_PLAT1") (pin "-") (pinfunction "-_-") (pintype "bidirectional"))
    )
    (net (code "79") (name "unconnected-(BESCHL_PLAT1-Pad--)") (class "Default")
      (node (ref "BESCHL_PLAT1") (pin "--") (pinfunction "--_--") (pintype "bidirectional"))
    )
    (net (code "80") (name "unconnected-(BESCHL_PLAT1-Pad---)") (class "Default")
      (node (ref "BESCHL_PLAT1") (pin "---") (pinfunction "---_---") (pintype "bidirectional"))
    )
    (net (code "81") (name "unconnected-(BESCHL_PLAT1-Pad----)") (class "Default")
      (node (ref "BESCHL_PLAT1") (pin "----") (pinfunction "----_----") (pintype "bidirectional"))
    )
    (net (code "82") (name "unconnected-(BESCHL_PLAT1-Pad-----)") (class "Default")
      (node (ref "BESCHL_PLAT1") (pin "-----") (pinfunction "-----_-----") (pintype "bidirectional"))
    )
    (net (code "83") (name "unconnected-(BESCHL_PLAT1-PadINT2)") (class "Default")
      (node (ref "BESCHL_PLAT1") (pin "INT2") (pinfunction "INT2_INT2") (pintype "bidirectional"))
    )
    (net (code "84") (name "unconnected-(U$1-Pad-)") (class "Default")
      (node (ref "U$1") (pin "-") (pinfunction "-_-") (pintype "bidirectional"))
    )
    (net (code "85") (name "unconnected-(U$1-PadINT)") (class "Default")
      (node (ref "U$1") (pin "INT") (pinfunction "INT_INT") (pintype "bidirectional"))
    )
    (net (code "86") (name "unconnected-(U$2-PadRESET)") (class "Default")
      (node (ref "U$2") (pin "RESET") (pinfunction "RESET_RESET") (pintype "bidirectional"))
    )
    (net (code "87") (name "unconnected-(U$2-PadRESET1)") (class "Default")
      (node (ref "U$2") (pin "RESET1") (pinfunction "RESET1_RESET1") (pintype "bidirectional"))
    )
    (net (code "88") (name "unconnected-(U$3-Pad3)") (class "Default")
      (node (ref "U$3") (pin "3") (pinfunction "3_3") (pintype "bidirectional"))
    )
    (net (code "89") (name "unconnected-(U$3-Pad8)") (class "Default")
      (node (ref "U$3") (pin "8") (pinfunction "8_8") (pintype "bidirectional"))
    )
    (net (code "90") (name "unconnected-(U$4-PadIN3)") (class "Default")
      (node (ref "U$4") (pin "IN3") (pinfunction "IN3_IN3") (pintype "bidirectional"))
    )
    (net (code "91") (name "unconnected-(U$4-PadOUT3)") (class "Default")
      (node (ref "U$4") (pin "OUT3") (pinfunction "OUT3_OUT3") (pintype "bidirectional"))
    )
    (net (code "92") (name "unconnected-(U$8-PadSDO)") (class "Default")
      (node (ref "U$8") (pin "SDO") (pinfunction "SDO_SDO") (pintype "bidirectional"))
    )
  )
)
